# SCH_Hermes_For_Production_2023-01-27.net
KiCad netlist of a schematic drawn in EasyEDA
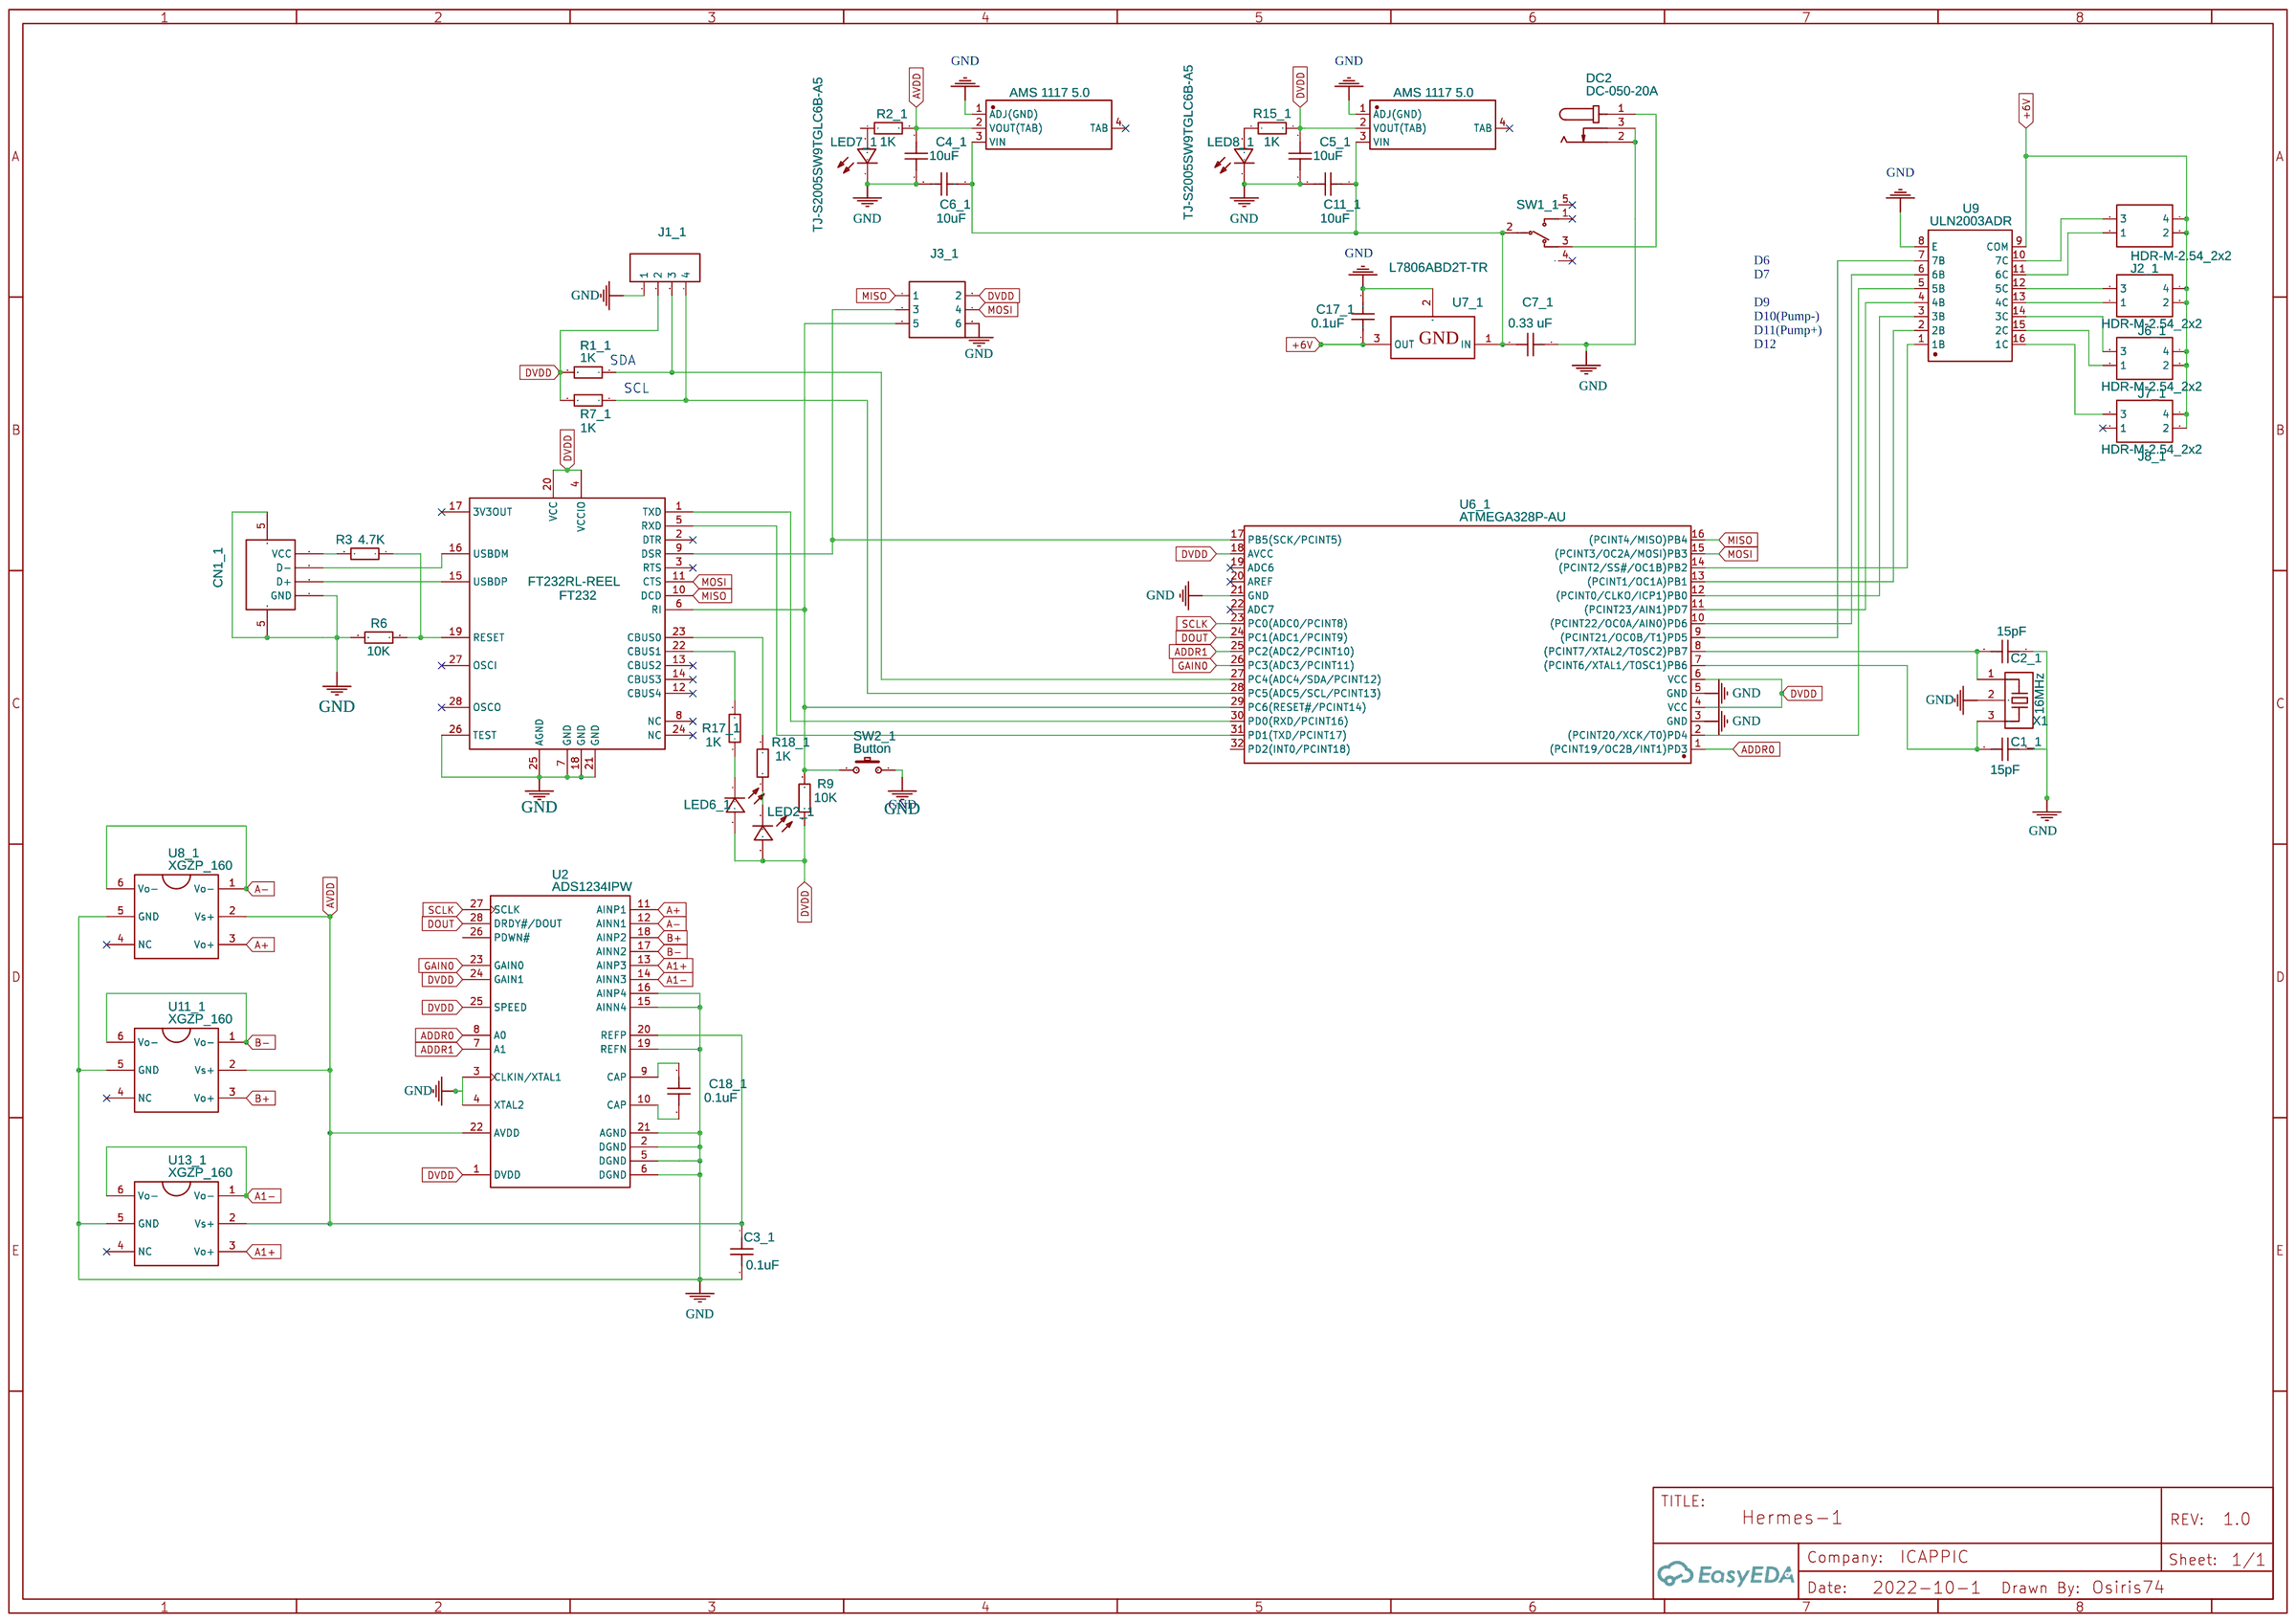
[diagram p0: schematic sheet]

(export (version "E")
  (design (tool "Eeschema 10.0.6"))
  (components
    (comp (ref "C1_1")
      (value "15pF")
      (fields
        (field (name "BOM_Manufacturer Part") "0402N150F500CT")
        (field (name "BOM_Supplier Part") "C396706")
      )
      (libsource (lib "") (part "0402N150F500CT_1"))
    )
    (comp (ref "C2_1")
      (value "15pF")
      (fields
        (field (name "BOM_Manufacturer Part") "0402N150F500CT")
        (field (name "BOM_Supplier Part") "C396706")
      )
      (libsource (lib "") (part "0402N150F500CT"))
    )
    (comp (ref "C3_1") (value "0.1uF") (libsource (lib "") (part "C_0201_US")))
    (comp (ref "C4_1")
      (value "10uF")
      (fields
        (field (name "BOM_Manufacturer Part") "CL10A106KP8NNNC")
        (field (name "BOM_Supplier Part") "C19702")
      )
      (libsource (lib "") (part "CL10A106KP8NNNC_1"))
    )
    (comp (ref "C5_1")
      (value "10uF")
      (fields
        (field (name "BOM_Manufacturer Part") "CL10A106KP8NNNC")
        (field (name "BOM_Supplier Part") "C19702")
      )
      (libsource (lib "") (part "CL10A106KP8NNNC_3"))
    )
    (comp (ref "C6_1")
      (value "10uF")
      (fields
        (field (name "BOM_Manufacturer Part") "CL10A106KP8NNNC")
        (field (name "BOM_Supplier Part") "C19702")
      )
      (libsource (lib "") (part "CL10A106KP8NNNC"))
    )
    (comp (ref "C7_1") (value "0.33 uF") (libsource (lib "") (part "C_0201_US_2")))
    (comp (ref "C11_1")
      (value "10uF")
      (fields
        (field (name "BOM_Manufacturer Part") "CL10A106KP8NNNC")
        (field (name "BOM_Supplier Part") "C19702")
      )
      (libsource (lib "") (part "CL10A106KP8NNNC_2"))
    )
    (comp (ref "C17_1") (value "0.1uF") (libsource (lib "") (part "C_0201_US_1")))
    (comp (ref "C18_1") (value "0.1uF") (libsource (lib "") (part "C_0201_US_3")))
    (comp (ref "CN1_1")
      (value "USB-B-Female-90")
      (fields (field (name "BOM_Manufacturer Part") "USB-BF90") (field (name "BOM_Supplier Part") "C46392"))
      (libsource (lib "") (part "USB-B-Female-90"))
    )
    (comp (ref "DC2")
      (value "DC-050-20A")
      (fields (field (name "BOM_Supplier Part") "C707276"))
      (libsource (lib "") (part "DC-050-20A"))
    )
    (comp (ref "FT232")
      (value "FT232RL-REEL")
      (fields (field (name "BOM_Supplier Part") "C8690"))
      (libsource (lib "") (part "FT232RL-REEL"))
    )
    (comp (ref "J1_1")
      (value "HDR-M-2.54_1x4")
      (fields (field (name "BOM_Supplier Part") "C124378"))
      (libsource (lib "") (part "HDR-M-2.54_1x4"))
    )
    (comp (ref "J2_1")
      (value "HDR-M-2.54_2x2")
      (fields (field (name "BOM_Supplier Part") "C66690"))
      (libsource (lib "") (part "HDR-M-2.54_2x2_1"))
    )
    (comp (ref "J3_1")
      (value "HDR-M-2.54_2x3")
      (fields (field (name "BOM_Supplier Part") "C65114"))
      (libsource (lib "") (part "HDR-M-2.54_2x3"))
    )
    (comp (ref "J6_1")
      (value "HDR-M-2.54_2x2")
      (fields (field (name "BOM_Supplier Part") "C66690"))
      (libsource (lib "") (part "HDR-M-2.54_2x2"))
    )
    (comp (ref "J7_1")
      (value "HDR-M-2.54_2x2")
      (fields (field (name "BOM_Supplier Part") "C66690"))
      (libsource (lib "") (part "HDR-M-2.54_2x2_2"))
    )
    (comp (ref "J8_1")
      (value "HDR-M-2.54_2x2")
      (fields (field (name "BOM_Supplier Part") "C66690"))
      (libsource (lib "") (part "HDR-M-2.54_2x2_3"))
    )
    (comp (ref "LED2_1")
      (value "TJ-S2005SW9TGLC6B-A5")
      (fields (field (name "BOM_Supplier Part") "C273624"))
      (libsource (lib "") (part "TJ-S2005SW9TGLC6B-A5_2"))
    )
    (comp (ref "LED6_1")
      (value "TJ-S2005SW9TGLC6B-A5")
      (fields (field (name "BOM_Supplier Part") "C273624"))
      (libsource (lib "") (part "TJ-S2005SW9TGLC6B-A5_3"))
    )
    (comp (ref "LED7_1")
      (value "TJ-S2005SW9TGLC6B-A5")
      (fields (field (name "BOM_Supplier Part") "C273624"))
      (libsource (lib "") (part "TJ-S2005SW9TGLC6B-A5_1"))
    )
    (comp (ref "LED8_1")
      (value "TJ-S2005SW9TGLC6B-A5")
      (fields (field (name "BOM_Supplier Part") "C273624"))
      (libsource (lib "") (part "TJ-S2005SW9TGLC6B-A5"))
    )
    (comp (ref "R1_1")
      (value "1K")
      (fields
        (field (name "BOM_Manufacturer Part") "0805W8F1001T5E")
        (field (name "BOM_Supplier Part") "C17513")
      )
      (libsource (lib "") (part "0805W8F1001T5E_2"))
    )
    (comp (ref "R2_1")
      (value "1K")
      (fields
        (field (name "BOM_Manufacturer Part") "0805W8F1001T5E")
        (field (name "BOM_Supplier Part") "C17513")
      )
      (libsource (lib "") (part "0805W8F1001T5E_1"))
    )
    (comp (ref "R3")
      (value "4.7K")
      (fields
        (field (name "BOM_Manufacturer Part") "0805W8F4701T5E")
        (field (name "BOM_Supplier Part") "C17673")
      )
      (libsource (lib "") (part "0805W8F4701T5E"))
    )
    (comp (ref "R6")
      (value "10K")
      (fields
        (field (name "BOM_Manufacturer Part") "0805W8F1002T5E")
        (field (name "BOM_Supplier Part") "C17414")
      )
      (libsource (lib "") (part "0805W8F1002T5E"))
    )
    (comp (ref "R7_1")
      (value "1K")
      (fields
        (field (name "BOM_Manufacturer Part") "0805W8F1001T5E")
        (field (name "BOM_Supplier Part") "C17513")
      )
      (libsource (lib "") (part "0805W8F1001T5E"))
    )
    (comp (ref "R9")
      (value "10K")
      (fields
        (field (name "BOM_Manufacturer Part") "0805W8F1002T5E")
        (field (name "BOM_Supplier Part") "C17414")
      )
      (libsource (lib "") (part "0805W8F1002T5E_1"))
    )
    (comp (ref "R15_1")
      (value "1K")
      (fields
        (field (name "BOM_Manufacturer Part") "0805W8F1001T5E")
        (field (name "BOM_Supplier Part") "C17513")
      )
      (libsource (lib "") (part "0805W8F1001T5E_3"))
    )
    (comp (ref "R17_1")
      (value "1K")
      (fields
        (field (name "BOM_Manufacturer Part") "0805W8F1001T5E")
        (field (name "BOM_Supplier Part") "C17513")
      )
      (libsource (lib "") (part "0805W8F1001T5E_4"))
    )
    (comp (ref "R18_1")
      (value "1K")
      (fields
        (field (name "BOM_Manufacturer Part") "0805W8F1001T5E")
        (field (name "BOM_Supplier Part") "C17513")
      )
      (libsource (lib "") (part "0805W8F1001T5E_5"))
    )
    (comp (ref "SW1_1")
      (value "MR-0-102-A03-0003-RS")
      (fields (field (name "BOM_Supplier Part") "C1788503"))
      (libsource (lib "") (part "MR-0-102-A03-0003-RS"))
    )
    (comp (ref "SW2_1")
      (value "Button")
      (fields
        (field (name "BOM_Manufacturer Part") "K2-1107ST-A4SW-06")
        (field (name "BOM_Supplier Part") "C118141")
      )
      (libsource (lib "") (part "Button"))
    )
    (comp (ref "U1_1")
      (value "AMS 1117 5.0")
      (fields
        (field (name "BOM_Manufacturer Part") "AMS1117-5.0")
        (field (name "BOM_Supplier Part") "C347223")
      )
      (libsource (lib "") (part "AMS1117-5.0_C347223"))
    )
    (comp (ref "U2")
      (value "ADS1234IPW")
      (fields (field (name "BOM_Supplier Part") "C67224"))
      (libsource (lib "") (part "ADS1234IPW"))
    )
    (comp (ref "U3_1")
      (value "AMS 1117 5.0")
      (fields
        (field (name "BOM_Manufacturer Part") "AMS1117-5.0")
        (field (name "BOM_Supplier Part") "C347223")
      )
      (libsource (lib "") (part "AMS1117-5.0_C347223_1"))
    )
    (comp (ref "U6_1")
      (value "ATMEGA328P-AU")
      (fields (field (name "BOM_Supplier Part") "C14877"))
      (libsource (lib "") (part "ATMEGA328P-AU"))
    )
    (comp (ref "U7_1")
      (value "L7806ABD2T-TR")
      (fields (field (name "BOM_Supplier Part") "C26467"))
      (libsource (lib "") (part "L7806ABD2T-TR"))
    )
    (comp (ref "U8_1")
      (value "XGZP_160")
      (fields (field (name "BOM_Manufacturer Part") "XGZP6857D"))
      (libsource (lib "") (part "XGZP6857D"))
    )
    (comp (ref "U9")
      (value "ULN2003ADR")
      (fields (field (name "BOM_Supplier Part") "C7512"))
      (libsource (lib "") (part "ULN2003ADR"))
    )
    (comp (ref "U11_1")
      (value "XGZP_160")
      (fields (field (name "BOM_Manufacturer Part") "XGZP6857D"))
      (libsource (lib "") (part "XGZP6857D_2"))
    )
    (comp (ref "U13_1")
      (value "XGZP_160")
      (fields (field (name "BOM_Manufacturer Part") "XGZP6857D"))
      (libsource (lib "") (part "XGZP6857D_1"))
    )
    (comp (ref "X1")
      (value "16MHz")
      (fields
        (field (name "BOM_Manufacturer Part") "CSTCE16M0V53-R0")
        (field (name "BOM_Supplier Part") "C32180")
      )
      (libsource (lib "") (part "CSTCE16M0V53-R0"))
    )
  )
  (nets
    (net (code "1") (name "+6V") (class "Default")
      (node (ref "C17_1") (pin "1") (pinfunction "1_1") (pintype "unspecified"))
      (node (ref "J2_1") (pin "2") (pinfunction "2_2") (pintype "input"))
      (node (ref "J2_1") (pin "4") (pinfunction "4_4") (pintype "input"))
      (node (ref "J6_1") (pin "2") (pinfunction "2_2") (pintype "input"))
      (node (ref "J6_1") (pin "4") (pinfunction "4_4") (pintype "input"))
      (node (ref "J7_1") (pin "2") (pinfunction "2_2") (pintype "input"))
      (node (ref "J7_1") (pin "4") (pinfunction "4_4") (pintype "input"))
      (node (ref "J8_1") (pin "2") (pinfunction "2_2") (pintype "input"))
      (node (ref "J8_1") (pin "4") (pinfunction "4_4") (pintype "input"))
      (node (ref "U7_1") (pin "3") (pinfunction "OUT_3") (pintype "passive"))
      (node (ref "U9") (pin "9") (pinfunction "COM_9") (pintype "unspecified"))
    )
    (net (code "2") (name "A+") (class "Default")
      (node (ref "U2") (pin "11") (pinfunction "AINP1_11") (pintype "unspecified"))
      (node (ref "U8_1") (pin "3") (pinfunction "Vo+_3") (pintype "unspecified"))
    )
    (net (code "3") (name "A-") (class "Default")
      (node (ref "U2") (pin "12") (pinfunction "AINN1_12") (pintype "unspecified"))
      (node (ref "U8_1") (pin "1") (pinfunction "Vo-_1") (pintype "unspecified"))
      (node (ref "U8_1") (pin "6") (pinfunction "Vo-_6") (pintype "unspecified"))
    )
    (net (code "4") (name "A1+") (class "Default")
      (node (ref "U13_1") (pin "3") (pinfunction "Vo+_3") (pintype "unspecified"))
      (node (ref "U2") (pin "13") (pinfunction "AINP3_13") (pintype "unspecified"))
    )
    (net (code "5") (name "A1-") (class "Default")
      (node (ref "U13_1") (pin "1") (pinfunction "Vo-_1") (pintype "unspecified"))
      (node (ref "U13_1") (pin "6") (pinfunction "Vo-_6") (pintype "unspecified"))
      (node (ref "U2") (pin "14") (pinfunction "AINN3_14") (pintype "unspecified"))
    )
    (net (code "6") (name "ADDR0") (class "Default")
      (node (ref "U2") (pin "8") (pinfunction "A0_8") (pintype "unspecified"))
      (node (ref "U6_1") (pin "1") (pinfunction "(PCINT19/OC2B/INT1)PD3_1") (pintype "unspecified"))
    )
    (net (code "7") (name "ADDR1") (class "Default")
      (node (ref "U2") (pin "7") (pinfunction "A1_7") (pintype "unspecified"))
      (node (ref "U6_1") (pin "25") (pinfunction "PC2(ADC2/PCINT10)_25") (pintype "unspecified"))
    )
    (net (code "8") (name "AVDD") (class "Default")
      (node (ref "C3_1") (pin "1") (pinfunction "1_1") (pintype "unspecified"))
      (node (ref "C4_1") (pin "1") (pinfunction "1_1") (pintype "unspecified"))
      (node (ref "R2_1") (pin "2") (pinfunction "2_2") (pintype "input"))
      (node (ref "U11_1") (pin "2") (pinfunction "Vs+_2") (pintype "unspecified"))
      (node (ref "U13_1") (pin "2") (pinfunction "Vs+_2") (pintype "unspecified"))
      (node (ref "U2") (pin "20") (pinfunction "REFP_20") (pintype "unspecified"))
      (node (ref "U2") (pin "22") (pinfunction "AVDD_22") (pintype "passive"))
      (node (ref "U3_1") (pin "2") (pinfunction "VOUT(TAB)_2") (pintype "unspecified"))
      (node (ref "U8_1") (pin "2") (pinfunction "Vs+_2") (pintype "unspecified"))
    )
    (net (code "9") (name "B+") (class "Default")
      (node (ref "U11_1") (pin "3") (pinfunction "Vo+_3") (pintype "unspecified"))
      (node (ref "U2") (pin "18") (pinfunction "AINP2_18") (pintype "unspecified"))
    )
    (net (code "10") (name "B-") (class "Default")
      (node (ref "U11_1") (pin "1") (pinfunction "Vo-_1") (pintype "unspecified"))
      (node (ref "U11_1") (pin "6") (pinfunction "Vo-_6") (pintype "unspecified"))
      (node (ref "U2") (pin "17") (pinfunction "AINN2_17") (pintype "unspecified"))
    )
    (net (code "11") (name "DOUT") (class "Default")
      (node (ref "U2") (pin "28") (pinfunction "DRDY#/DOUT_28") (pintype "output"))
      (node (ref "U6_1") (pin "24") (pinfunction "PC1(ADC1/PCINT9)_24") (pintype "unspecified"))
    )
    (net (code "12") (name "DVDD") (class "Default")
      (node (ref "C5_1") (pin "1") (pinfunction "1_1") (pintype "unspecified"))
      (node (ref "FT232") (pin "20") (pinfunction "VCC_20") (pintype "passive"))
      (node (ref "FT232") (pin "4") (pinfunction "VCCIO_4") (pintype "passive"))
      (node (ref "J1_1") (pin "2") (pinfunction "2_2") (pintype "unspecified"))
      (node (ref "J3_1") (pin "2") (pinfunction "2_2") (pintype "input"))
      (node (ref "LED2_1") (pin "2") (pinfunction "2_2") (pintype "unspecified"))
      (node (ref "LED6_1") (pin "2") (pinfunction "2_2") (pintype "unspecified"))
      (node (ref "R15_1") (pin "2") (pinfunction "2_2") (pintype "input"))
      (node (ref "R1_1") (pin "2") (pinfunction "2_2") (pintype "input"))
      (node (ref "R7_1") (pin "2") (pinfunction "2_2") (pintype "input"))
      (node (ref "R9") (pin "1") (pinfunction "1_1") (pintype "input"))
      (node (ref "U1_1") (pin "2") (pinfunction "VOUT(TAB)_2") (pintype "unspecified"))
      (node (ref "U2") (pin "1") (pinfunction "DVDD_1") (pintype "passive"))
      (node (ref "U2") (pin "24") (pinfunction "GAIN1_24") (pintype "unspecified"))
      (node (ref "U2") (pin "25") (pinfunction "SPEED_25") (pintype "unspecified"))
      (node (ref "U6_1") (pin "18") (pinfunction "AVCC_18") (pintype "unspecified"))
      (node (ref "U6_1") (pin "4") (pinfunction "VCC_4") (pintype "unspecified"))
      (node (ref "U6_1") (pin "6") (pinfunction "VCC_6") (pintype "unspecified"))
    )
    (net (code "13") (name "GAIN0") (class "Default")
      (node (ref "U2") (pin "23") (pinfunction "GAIN0_23") (pintype "unspecified"))
      (node (ref "U6_1") (pin "26") (pinfunction "PC3(ADC3/PCINT11)_26") (pintype "unspecified"))
    )
    (net (code "14") (name "GND") (class "Default")
      (node (ref "C11_1") (pin "2") (pinfunction "2_2") (pintype "unspecified"))
      (node (ref "C17_1") (pin "2") (pinfunction "2_2") (pintype "unspecified"))
      (node (ref "C1_1") (pin "1") (pinfunction "1_1") (pintype "unspecified"))
      (node (ref "C2_1") (pin "1") (pinfunction "1_1") (pintype "unspecified"))
      (node (ref "C3_1") (pin "2") (pinfunction "2_2") (pintype "unspecified"))
      (node (ref "C4_1") (pin "2") (pinfunction "2_2") (pintype "unspecified"))
      (node (ref "C5_1") (pin "2") (pinfunction "2_2") (pintype "unspecified"))
      (node (ref "C6_1") (pin "2") (pinfunction "2_2") (pintype "unspecified"))
      (node (ref "C7_1") (pin "2") (pinfunction "2_2") (pintype "unspecified"))
      (node (ref "CN1_1") (pin "4") (pinfunction "GND_4") (pintype "input"))
      (node (ref "CN1_1") (pin "5") (pinfunction "SH2_5") (pintype "unspecified"))
      (node (ref "DC2") (pin "2") (pinfunction "2_2") (pintype "unspecified"))
      (node (ref "DC2") (pin "3") (pinfunction "3_3") (pintype "unspecified"))
      (node (ref "FT232") (pin "18") (pinfunction "GND_18") (pintype "passive"))
      (node (ref "FT232") (pin "21") (pinfunction "GND_21") (pintype "passive"))
      (node (ref "FT232") (pin "25") (pinfunction "AGND_25") (pintype "passive"))
      (node (ref "FT232") (pin "26") (pinfunction "TEST_26") (pintype "unspecified"))
      (node (ref "FT232") (pin "7") (pinfunction "GND_7") (pintype "passive"))
      (node (ref "J1_1") (pin "1") (pinfunction "1_1") (pintype "unspecified"))
      (node (ref "J3_1") (pin "6") (pinfunction "6_6") (pintype "input"))
      (node (ref "LED7_1") (pin "1") (pinfunction "1_1") (pintype "unspecified"))
      (node (ref "LED8_1") (pin "1") (pinfunction "1_1") (pintype "unspecified"))
      (node (ref "R6") (pin "2") (pinfunction "2_2") (pintype "input"))
      (node (ref "SW2_1") (pin "2") (pinfunction "2_2") (pintype "unspecified"))
      (node (ref "U11_1") (pin "5") (pinfunction "GND_5") (pintype "unspecified"))
      (node (ref "U13_1") (pin "5") (pinfunction "GND_5") (pintype "unspecified"))
      (node (ref "U1_1") (pin "1") (pinfunction "ADJ(GND)_1") (pintype "unspecified"))
      (node (ref "U2") (pin "15") (pinfunction "AINN4_15") (pintype "unspecified"))
      (node (ref "U2") (pin "16") (pinfunction "AINP4_16") (pintype "unspecified"))
      (node (ref "U2") (pin "19") (pinfunction "REFN_19") (pintype "unspecified"))
      (node (ref "U2") (pin "2") (pinfunction "DGND_2") (pintype "passive"))
      (node (ref "U2") (pin "21") (pinfunction "AGND_21") (pintype "passive"))
      (node (ref "U2") (pin "3") (pinfunction "CLKIN/XTAL1_3") (pintype "unspecified"))
      (node (ref "U2") (pin "4") (pinfunction "XTAL2_4") (pintype "unspecified"))
      (node (ref "U2") (pin "5") (pinfunction "DGND_5") (pintype "passive"))
      (node (ref "U2") (pin "6") (pinfunction "DGND_6") (pintype "passive"))
      (node (ref "U3_1") (pin "1") (pinfunction "ADJ(GND)_1") (pintype "unspecified"))
      (node (ref "U6_1") (pin "21") (pinfunction "GND_21") (pintype "unspecified"))
      (node (ref "U6_1") (pin "3") (pinfunction "GND_3") (pintype "unspecified"))
      (node (ref "U6_1") (pin "5") (pinfunction "GND_5") (pintype "unspecified"))
      (node (ref "U7_1") (pin "2") (pinfunction "GND_2") (pintype "passive"))
      (node (ref "U8_1") (pin "5") (pinfunction "GND_5") (pintype "unspecified"))
      (node (ref "U9") (pin "8") (pinfunction "E_8") (pintype "unspecified"))
      (node (ref "X1") (pin "2") (pinfunction "2_2") (pintype "unspecified"))
    )
    (net (code "15") (name "MISO") (class "Default")
      (node (ref "FT232") (pin "10") (pinfunction "DCD_10") (pintype "unspecified"))
      (node (ref "J3_1") (pin "1") (pinfunction "1_1") (pintype "input"))
      (node (ref "U6_1") (pin "16") (pinfunction "(PCINT4/MISO)PB4_16") (pintype "unspecified"))
    )
    (net (code "16") (name "MOSI") (class "Default")
      (node (ref "FT232") (pin "11") (pinfunction "CTS_11") (pintype "unspecified"))
      (node (ref "J3_1") (pin "4") (pinfunction "4_4") (pintype "input"))
      (node (ref "U6_1") (pin "15") (pinfunction "(PCINT3/OC2A/MOSI)PB3_15") (pintype "unspecified"))
    )
    (net (code "17") (name "Net-(C18_1-Pad1)") (class "Default")
      (node (ref "C18_1") (pin "1") (pinfunction "1_1") (pintype "unspecified"))
      (node (ref "U2") (pin "9") (pinfunction "CAP_9") (pintype "unspecified"))
    )
    (net (code "18") (name "Net-(C18_1-Pad2)") (class "Default")
      (node (ref "C18_1") (pin "2") (pinfunction "2_2") (pintype "unspecified"))
      (node (ref "U2") (pin "10") (pinfunction "CAP_10") (pintype "unspecified"))
    )
    (net (code "19") (name "Net-(CN1_1-D+)") (class "Default")
      (node (ref "CN1_1") (pin "3") (pinfunction "D+_3") (pintype "input"))
      (node (ref "FT232") (pin "15") (pinfunction "USBDP_15") (pintype "bidirectional"))
    )
    (net (code "20") (name "Net-(CN1_1-D-)") (class "Default")
      (node (ref "CN1_1") (pin "2") (pinfunction "D-_2") (pintype "input"))
      (node (ref "FT232") (pin "16") (pinfunction "USBDM_16") (pintype "bidirectional"))
    )
    (net (code "21") (name "Net-(CN1_1-VCC)") (class "Default")
      (node (ref "CN1_1") (pin "1") (pinfunction "VCC_1") (pintype "input"))
      (node (ref "R3") (pin "2") (pinfunction "2_2") (pintype "input"))
    )
    (net (code "22") (name "Net-(DC2-Pad1)") (class "Default")
      (node (ref "DC2") (pin "1") (pinfunction "1_1") (pintype "unspecified"))
      (node (ref "SW1_1") (pin "3") (pinfunction "3_3") (pintype "unspecified"))
    )
    (net (code "23") (name "Net-(FT232-CBUS0)") (class "Default")
      (node (ref "FT232") (pin "23") (pinfunction "CBUS0_23") (pintype "bidirectional"))
      (node (ref "R18_1") (pin "2") (pinfunction "2_2") (pintype "input"))
    )
    (net (code "24") (name "Net-(FT232-CBUS1)") (class "Default")
      (node (ref "FT232") (pin "22") (pinfunction "CBUS1_22") (pintype "bidirectional"))
      (node (ref "R17_1") (pin "2") (pinfunction "2_2") (pintype "input"))
    )
    (net (code "25") (name "Net-(FT232-DSR)") (class "Default")
      (node (ref "FT232") (pin "9") (pinfunction "DSR_9") (pintype "unspecified"))
      (node (ref "J3_1") (pin "3") (pinfunction "3_3") (pintype "input"))
      (node (ref "U6_1") (pin "17") (pinfunction "PB5(SCK/PCINT5)_17") (pintype "unspecified"))
    )
    (net (code "26") (name "Net-(FT232-RESET)") (class "Default")
      (node (ref "FT232") (pin "19") (pinfunction "RESET_19") (pintype "unspecified"))
      (node (ref "R3") (pin "1") (pinfunction "1_1") (pintype "input"))
      (node (ref "R6") (pin "1") (pinfunction "1_1") (pintype "input"))
    )
    (net (code "27") (name "Net-(FT232-RI)") (class "Default")
      (node (ref "FT232") (pin "6") (pinfunction "RI_6") (pintype "unspecified"))
      (node (ref "J3_1") (pin "5") (pinfunction "5_5") (pintype "input"))
      (node (ref "R9") (pin "2") (pinfunction "2_2") (pintype "input"))
      (node (ref "SW2_1") (pin "1") (pinfunction "1_1") (pintype "unspecified"))
      (node (ref "U6_1") (pin "29") (pinfunction "PC6(RESET#/PCINT14)_29") (pintype "unspecified"))
    )
    (net (code "28") (name "Net-(FT232-RXD)") (class "Default")
      (node (ref "FT232") (pin "5") (pinfunction "RXD_5") (pintype "unspecified"))
      (node (ref "U6_1") (pin "31") (pinfunction "PD1(TXD/PCINT17)_31") (pintype "unspecified"))
    )
    (net (code "29") (name "Net-(FT232-TXD)") (class "Default")
      (node (ref "FT232") (pin "1") (pinfunction "TXD_1") (pintype "output"))
      (node (ref "U6_1") (pin "30") (pinfunction "PD0(RXD/PCINT16)_30") (pintype "unspecified"))
    )
    (net (code "30") (name "Net-(LED2_1-Pad1)") (class "Default")
      (node (ref "LED2_1") (pin "1") (pinfunction "1_1") (pintype "unspecified"))
      (node (ref "R18_1") (pin "1") (pinfunction "1_1") (pintype "input"))
    )
    (net (code "31") (name "Net-(LED6_1-Pad1)") (class "Default")
      (node (ref "LED6_1") (pin "1") (pinfunction "1_1") (pintype "unspecified"))
      (node (ref "R17_1") (pin "1") (pinfunction "1_1") (pintype "input"))
    )
    (net (code "32") (name "Net-(LED7_1-Pad2)") (class "Default")
      (node (ref "LED7_1") (pin "2") (pinfunction "2_2") (pintype "unspecified"))
      (node (ref "R2_1") (pin "1") (pinfunction "1_1") (pintype "input"))
    )
    (net (code "33") (name "Net-(LED8_1-Pad2)") (class "Default")
      (node (ref "LED8_1") (pin "2") (pinfunction "2_2") (pintype "unspecified"))
      (node (ref "R15_1") (pin "1") (pinfunction "1_1") (pintype "input"))
    )
    (net (code "34") (name "Net-(U1_1-VIN)") (class "Default")
      (node (ref "C11_1") (pin "1") (pinfunction "1_1") (pintype "unspecified"))
      (node (ref "C6_1") (pin "1") (pinfunction "1_1") (pintype "unspecified"))
      (node (ref "C7_1") (pin "1") (pinfunction "1_1") (pintype "unspecified"))
      (node (ref "SW1_1") (pin "2") (pinfunction "2_2") (pintype "unspecified"))
      (node (ref "U1_1") (pin "3") (pinfunction "VIN_3") (pintype "unspecified"))
      (node (ref "U3_1") (pin "3") (pinfunction "VIN_3") (pintype "unspecified"))
      (node (ref "U7_1") (pin "1") (pinfunction "IN_1") (pintype "passive"))
    )
    (net (code "35") (name "Net-(U6_1-(PCINT0{slash}CLKO{slash}ICP1)PB0)") (class "Default")
      (node (ref "U6_1") (pin "12") (pinfunction "(PCINT0/CLKO/ICP1)PB0_12") (pintype "unspecified"))
      (node (ref "U9") (pin "3") (pinfunction "3B_3") (pintype "unspecified"))
    )
    (net (code "36") (name "Net-(U6_1-(PCINT1{slash}OC1A)PB1)") (class "Default")
      (node (ref "U6_1") (pin "13") (pinfunction "(PCINT1/OC1A)PB1_13") (pintype "unspecified"))
      (node (ref "U9") (pin "2") (pinfunction "2B_2") (pintype "unspecified"))
    )
    (net (code "37") (name "Net-(U6_1-(PCINT2{slash}SS#{slash}OC1B)PB2)") (class "Default")
      (node (ref "U6_1") (pin "14") (pinfunction "(PCINT2/SS#/OC1B)PB2_14") (pintype "unspecified"))
      (node (ref "U9") (pin "1") (pinfunction "1B_1") (pintype "unspecified"))
    )
    (net (code "38") (name "Net-(U6_1-(PCINT6{slash}XTAL1{slash}TOSC1)PB6)") (class "Default")
      (node (ref "C1_1") (pin "2") (pinfunction "2_2") (pintype "unspecified"))
      (node (ref "U6_1") (pin "7") (pinfunction "(PCINT6/XTAL1/TOSC1)PB6_7") (pintype "unspecified"))
      (node (ref "X1") (pin "3") (pinfunction "3_3") (pintype "unspecified"))
    )
    (net (code "39") (name "Net-(U6_1-(PCINT7{slash}XTAL2{slash}TOSC2)PB7)") (class "Default")
      (node (ref "C2_1") (pin "2") (pinfunction "2_2") (pintype "unspecified"))
      (node (ref "U6_1") (pin "8") (pinfunction "(PCINT7/XTAL2/TOSC2)PB7_8") (pintype "unspecified"))
      (node (ref "X1") (pin "1") (pinfunction "1_1") (pintype "unspecified"))
    )
    (net (code "40") (name "Net-(U6_1-(PCINT20{slash}XCK{slash}T0)PD4)") (class "Default")
      (node (ref "U6_1") (pin "2") (pinfunction "(PCINT20/XCK/T0)PD4_2") (pintype "unspecified"))
      (node (ref "U9") (pin "5") (pinfunction "5B_5") (pintype "unspecified"))
    )
    (net (code "41") (name "Net-(U6_1-(PCINT21{slash}OC0B{slash}T1)PD5)") (class "Default")
      (node (ref "U6_1") (pin "9") (pinfunction "(PCINT21/OC0B/T1)PD5_9") (pintype "unspecified"))
      (node (ref "U9") (pin "7") (pinfunction "7B_7") (pintype "unspecified"))
    )
    (net (code "42") (name "Net-(U6_1-(PCINT22{slash}OC0A{slash}AIN0)PD6)") (class "Default")
      (node (ref "U6_1") (pin "10") (pinfunction "(PCINT22/OC0A/AIN0)PD6_10") (pintype "unspecified"))
      (node (ref "U9") (pin "6") (pinfunction "6B_6") (pintype "unspecified"))
    )
    (net (code "43") (name "Net-(U6_1-(PCINT23{slash}AIN1)PD7)") (class "Default")
      (node (ref "U6_1") (pin "11") (pinfunction "(PCINT23/AIN1)PD7_11") (pintype "unspecified"))
      (node (ref "U9") (pin "4") (pinfunction "4B_4") (pintype "unspecified"))
    )
    (net (code "44") (name "Net-(U6_1-PC4(ADC4{slash}SDA{slash}PCINT12))") (class "Default")
      (node (ref "J1_1") (pin "3") (pinfunction "3_3") (pintype "unspecified"))
      (node (ref "R1_1") (pin "1") (pinfunction "1_1") (pintype "input"))
      (node (ref "U6_1") (pin "27") (pinfunction "PC4(ADC4/SDA/PCINT12)_27") (pintype "unspecified"))
    )
    (net (code "45") (name "Net-(U6_1-PC5(ADC5{slash}SCL{slash}PCINT13))") (class "Default")
      (node (ref "J1_1") (pin "4") (pinfunction "4_4") (pintype "unspecified"))
      (node (ref "R7_1") (pin "1") (pinfunction "1_1") (pintype "input"))
      (node (ref "U6_1") (pin "28") (pinfunction "PC5(ADC5/SCL/PCINT13)_28") (pintype "unspecified"))
    )
    (net (code "46") (name "Net-(U9-1C)") (class "Default")
      (node (ref "J8_1") (pin "3") (pinfunction "3_3") (pintype "input"))
      (node (ref "U9") (pin "16") (pinfunction "1C_16") (pintype "unspecified"))
    )
    (net (code "47") (name "Net-(U9-2C)") (class "Default")
      (node (ref "J7_1") (pin "1") (pinfunction "1_1") (pintype "input"))
      (node (ref "U9") (pin "15") (pinfunction "2C_15") (pintype "unspecified"))
    )
    (net (code "48") (name "Net-(U9-3C)") (class "Default")
      (node (ref "J7_1") (pin "3") (pinfunction "3_3") (pintype "input"))
      (node (ref "U9") (pin "14") (pinfunction "3C_14") (pintype "unspecified"))
    )
    (net (code "49") (name "Net-(U9-4C)") (class "Default")
      (node (ref "J6_1") (pin "1") (pinfunction "1_1") (pintype "input"))
      (node (ref "U9") (pin "13") (pinfunction "4C_13") (pintype "unspecified"))
    )
    (net (code "50") (name "Net-(U9-5C)") (class "Default")
      (node (ref "J6_1") (pin "3") (pinfunction "3_3") (pintype "input"))
      (node (ref "U9") (pin "12") (pinfunction "5C_12") (pintype "unspecified"))
    )
    (net (code "51") (name "Net-(U9-6C)") (class "Default")
      (node (ref "J2_1") (pin "1") (pinfunction "1_1") (pintype "input"))
      (node (ref "U9") (pin "11") (pinfunction "6C_11") (pintype "unspecified"))
    )
    (net (code "52") (name "Net-(U9-7C)") (class "Default")
      (node (ref "J2_1") (pin "3") (pinfunction "3_3") (pintype "input"))
      (node (ref "U9") (pin "10") (pinfunction "7C_10") (pintype "unspecified"))
    )
    (net (code "53") (name "SCLK") (class "Default")
      (node (ref "U2") (pin "27") (pinfunction "SCLK_27") (pintype "unspecified"))
      (node (ref "U6_1") (pin "23") (pinfunction "PC0(ADC0/PCINT8)_23") (pintype "unspecified"))
    )
    (net (code "54") (name "unconnected-(FT232-3V3OUT-Pad17)") (class "Default")
      (node (ref "FT232") (pin "17") (pinfunction "3V3OUT_17") (pintype "output"))
    )
    (net (code "55") (name "unconnected-(FT232-CBUS2-Pad13)") (class "Default")
      (node (ref "FT232") (pin "13") (pinfunction "CBUS2_13") (pintype "bidirectional"))
    )
    (net (code "56") (name "unconnected-(FT232-CBUS3-Pad14)") (class "Default")
      (node (ref "FT232") (pin "14") (pinfunction "CBUS3_14") (pintype "bidirectional"))
    )
    (net (code "57") (name "unconnected-(FT232-CBUS4-Pad12)") (class "Default")
      (node (ref "FT232") (pin "12") (pinfunction "CBUS4_12") (pintype "bidirectional"))
    )
    (net (code "58") (name "unconnected-(FT232-DTR-Pad2)") (class "Default")
      (node (ref "FT232") (pin "2") (pinfunction "DTR_2") (pintype "output+no_connect"))
    )
    (net (code "59") (name "unconnected-(FT232-NC-Pad8)") (class "Default")
      (node (ref "FT232") (pin "8") (pinfunction "NC_8") (pintype "unspecified"))
    )
    (net (code "60") (name "unconnected-(FT232-NC-Pad24)") (class "Default")
      (node (ref "FT232") (pin "24") (pinfunction "NC_24") (pintype "unspecified"))
    )
    (net (code "61") (name "unconnected-(FT232-OSCI-Pad27)") (class "Default")
      (node (ref "FT232") (pin "27") (pinfunction "OSCI_27") (pintype "unspecified"))
    )
    (net (code "62") (name "unconnected-(FT232-OSCO-Pad28)") (class "Default")
      (node (ref "FT232") (pin "28") (pinfunction "OSCO_28") (pintype "output"))
    )
    (net (code "63") (name "unconnected-(FT232-RTS-Pad3)") (class "Default")
      (node (ref "FT232") (pin "3") (pinfunction "RTS_3") (pintype "output"))
    )
    (net (code "64") (name "unconnected-(J8_1-Pad1)") (class "Default")
      (node (ref "J8_1") (pin "1") (pinfunction "1_1") (pintype "input+no_connect"))
    )
    (net (code "65") (name "unconnected-(SW1_1-Pad1)") (class "Default")
      (node (ref "SW1_1") (pin "1") (pinfunction "1_1") (pintype "unspecified+no_connect"))
    )
    (net (code "66") (name "unconnected-(SW1_1-Pad4)") (class "Default")
      (node (ref "SW1_1") (pin "4") (pinfunction "4_4") (pintype "unspecified+no_connect"))
    )
    (net (code "67") (name "unconnected-(SW1_1-Pad5)") (class "Default")
      (node (ref "SW1_1") (pin "5") (pinfunction "5_5") (pintype "unspecified+no_connect"))
    )
    (net (code "68") (name "unconnected-(U1_1-TAB-Pad4)") (class "Default")
      (node (ref "U1_1") (pin "4") (pinfunction "TAB_4") (pintype "unspecified"))
    )
    (net (code "69") (name "unconnected-(U2-PDWN#-Pad26)") (class "Default")
      (node (ref "U2") (pin "26") (pinfunction "PDWN#_26") (pintype "unspecified"))
    )
    (net (code "70") (name "unconnected-(U3_1-TAB-Pad4)") (class "Default")
      (node (ref "U3_1") (pin "4") (pinfunction "TAB_4") (pintype "unspecified"))
    )
    (net (code "71") (name "unconnected-(U6_1-ADC6-Pad19)") (class "Default")
      (node (ref "U6_1") (pin "19") (pinfunction "ADC6_19") (pintype "unspecified+no_connect"))
    )
    (net (code "72") (name "unconnected-(U6_1-ADC7-Pad22)") (class "Default")
      (node (ref "U6_1") (pin "22") (pinfunction "ADC7_22") (pintype "unspecified+no_connect"))
    )
    (net (code "73") (name "unconnected-(U6_1-AREF-Pad20)") (class "Default")
      (node (ref "U6_1") (pin "20") (pinfunction "AREF_20") (pintype "unspecified+no_connect"))
    )
    (net (code "74") (name "unconnected-(U6_1-PD2(INT0{slash}PCINT18)-Pad32)") (class "Default")
      (node (ref "U6_1") (pin "32") (pinfunction "PD2(INT0/PCINT18)_32") (pintype "unspecified"))
    )
    (net (code "75") (name "unconnected-(U8_1-NC-Pad4)") (class "Default")
      (node (ref "U8_1") (pin "4") (pinfunction "NC_4") (pintype "unspecified"))
    )
    (net (code "76") (name "unconnected-(U11_1-NC-Pad4)") (class "Default")
      (node (ref "U11_1") (pin "4") (pinfunction "NC_4") (pintype "unspecified"))
    )
    (net (code "77") (name "unconnected-(U13_1-NC-Pad4)") (class "Default")
      (node (ref "U13_1") (pin "4") (pinfunction "NC_4") (pintype "unspecified"))
    )
  )
)
